# and08479_Individual.net
KiCad netlist of a schematic drawn in Altium Designer
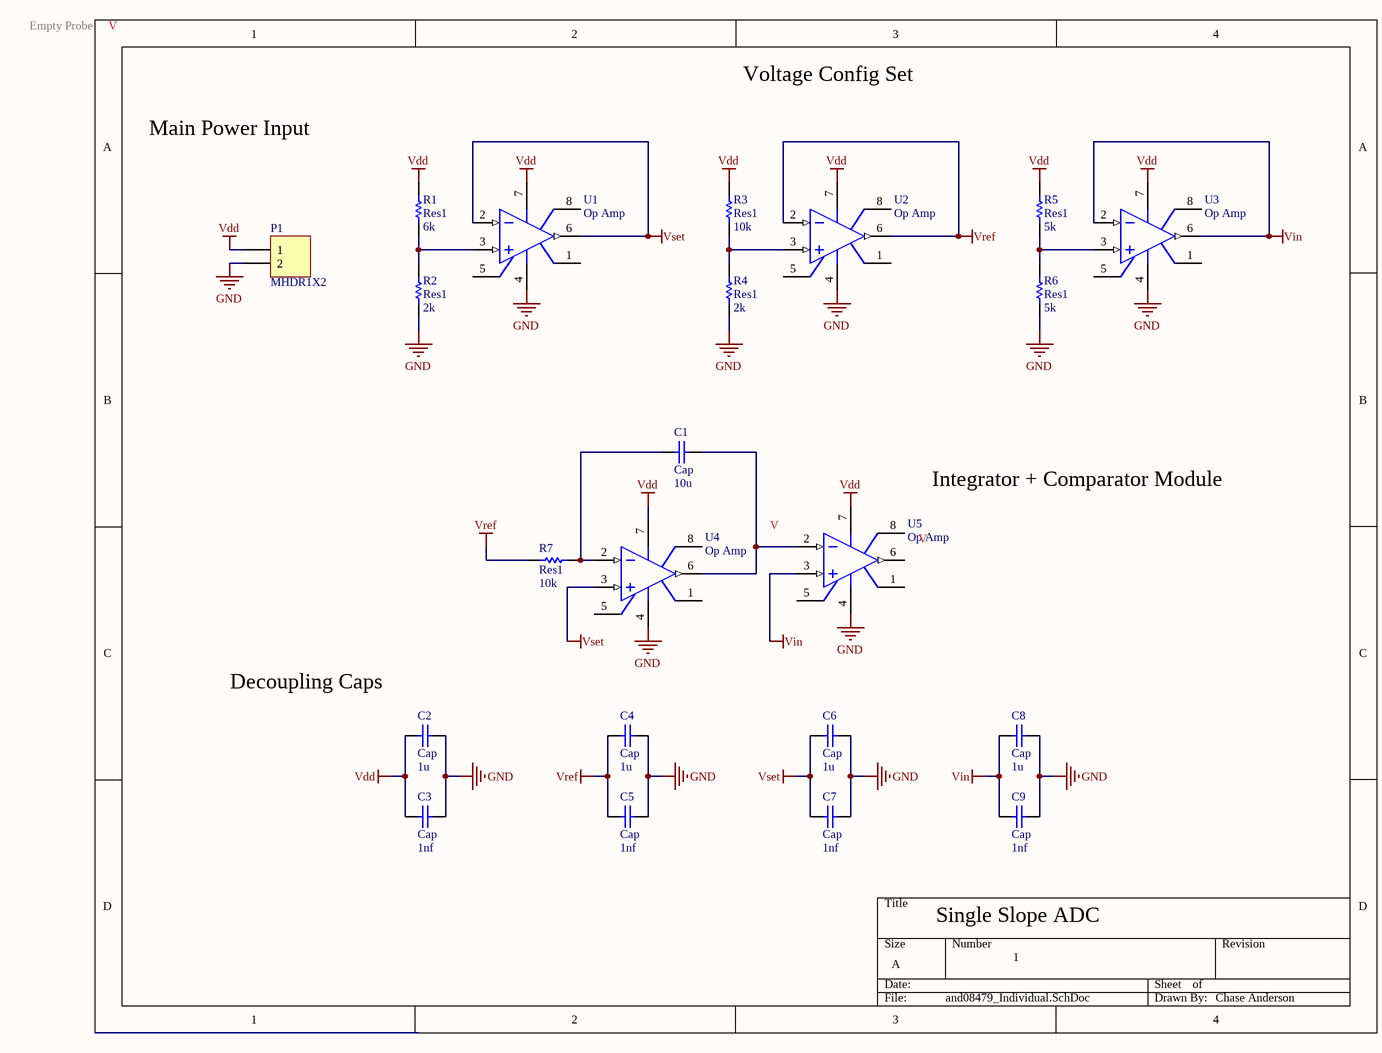
[diagram p0: and08479_Individual.SchDoc]

(export (version "E")
  (design (tool "Eeschema 10.0.6"))
  (components
    (comp (ref "C1")
      (value "Cap")
      (footprint "RAD-0.3")
      (description "Capacitor")
      (fields (field (name "ALTIUM_VALUE") "10u") (field (name "PUBLISHER") "Altium Limited"))
      (libsource (lib "Miscellaneous Devices") (part "Cap"))
    )
    (comp (ref "C2")
      (value "Cap")
      (footprint "RAD-0.3")
      (description "Capacitor")
      (fields (field (name "ALTIUM_VALUE") "1u") (field (name "PUBLISHER") "Altium Limited"))
      (libsource (lib "Miscellaneous Devices") (part "Cap"))
    )
    (comp (ref "C3")
      (value "Cap")
      (footprint "RAD-0.3")
      (description "Capacitor")
      (fields (field (name "ALTIUM_VALUE") "1nf") (field (name "PUBLISHER") "Altium Limited"))
      (libsource (lib "Miscellaneous Devices") (part "Cap"))
    )
    (comp (ref "C4")
      (value "Cap")
      (footprint "RAD-0.3")
      (description "Capacitor")
      (fields (field (name "ALTIUM_VALUE") "1u") (field (name "PUBLISHER") "Altium Limited"))
      (libsource (lib "Miscellaneous Devices") (part "Cap"))
    )
    (comp (ref "C5")
      (value "Cap")
      (footprint "RAD-0.3")
      (description "Capacitor")
      (fields (field (name "ALTIUM_VALUE") "1nf") (field (name "PUBLISHER") "Altium Limited"))
      (libsource (lib "Miscellaneous Devices") (part "Cap"))
    )
    (comp (ref "C6")
      (value "Cap")
      (footprint "RAD-0.3")
      (description "Capacitor")
      (fields (field (name "ALTIUM_VALUE") "1u") (field (name "PUBLISHER") "Altium Limited"))
      (libsource (lib "Miscellaneous Devices") (part "Cap"))
    )
    (comp (ref "C7")
      (value "Cap")
      (footprint "RAD-0.3")
      (description "Capacitor")
      (fields (field (name "ALTIUM_VALUE") "1nf") (field (name "PUBLISHER") "Altium Limited"))
      (libsource (lib "Miscellaneous Devices") (part "Cap"))
    )
    (comp (ref "C8")
      (value "Cap")
      (footprint "RAD-0.3")
      (description "Capacitor")
      (fields (field (name "ALTIUM_VALUE") "1u") (field (name "PUBLISHER") "Altium Limited"))
      (libsource (lib "Miscellaneous Devices") (part "Cap"))
    )
    (comp (ref "C9")
      (value "Cap")
      (footprint "RAD-0.3")
      (description "Capacitor")
      (fields (field (name "ALTIUM_VALUE") "1nf") (field (name "PUBLISHER") "Altium Limited"))
      (libsource (lib "Miscellaneous Devices") (part "Cap"))
    )
    (comp (ref "P1")
      (value "MHDR1X2")
      (footprint "MHDR1X2")
      (description "Header, 2-Pin")
      (fields (field (name "PUBLISHER") "Altium Limited"))
      (libsource (lib "Miscellaneous Connectors") (part "MHDR1X2"))
    )
    (comp (ref "R1")
      (value "Res1")
      (footprint "AXIAL-0.3")
      (description "Resistor")
      (fields (field (name "ALTIUM_VALUE") "6k") (field (name "PUBLISHER") "Altium Limited"))
      (libsource (lib "Miscellaneous Devices") (part "Res1"))
    )
    (comp (ref "R2")
      (value "Res1")
      (footprint "AXIAL-0.3")
      (description "Resistor")
      (fields (field (name "ALTIUM_VALUE") "2k") (field (name "PUBLISHER") "Altium Limited"))
      (libsource (lib "Miscellaneous Devices") (part "Res1"))
    )
    (comp (ref "R3")
      (value "Res1")
      (footprint "AXIAL-0.3")
      (description "Resistor")
      (fields (field (name "ALTIUM_VALUE") "10k") (field (name "PUBLISHER") "Altium Limited"))
      (libsource (lib "Miscellaneous Devices") (part "Res1"))
    )
    (comp (ref "R4")
      (value "Res1")
      (footprint "AXIAL-0.3")
      (description "Resistor")
      (fields (field (name "ALTIUM_VALUE") "2k") (field (name "PUBLISHER") "Altium Limited"))
      (libsource (lib "Miscellaneous Devices") (part "Res1"))
    )
    (comp (ref "R5")
      (value "Res1")
      (footprint "AXIAL-0.3")
      (description "Resistor")
      (fields (field (name "ALTIUM_VALUE") "5k") (field (name "PUBLISHER") "Altium Limited"))
      (libsource (lib "Miscellaneous Devices") (part "Res1"))
    )
    (comp (ref "R6")
      (value "Res1")
      (footprint "AXIAL-0.3")
      (description "Resistor")
      (fields (field (name "ALTIUM_VALUE") "5k") (field (name "PUBLISHER") "Altium Limited"))
      (libsource (lib "Miscellaneous Devices") (part "Res1"))
    )
    (comp (ref "R7")
      (value "Res1")
      (footprint "AXIAL-0.3")
      (description "Resistor")
      (fields (field (name "ALTIUM_VALUE") "10k") (field (name "PUBLISHER") "Altium Limited"))
      (libsource (lib "Miscellaneous Devices") (part "Res1"))
    )
    (comp (ref "U1")
      (value "Op Amp")
      (footprint "H-08A")
      (description "FET Operational Amplifier")
      (fields (field (name "PUBLISHER") "Altium Limited"))
      (libsource (lib "Miscellaneous Devices") (part "Op Amp"))
    )
    (comp (ref "U2")
      (value "Op Amp")
      (footprint "H-08A")
      (description "FET Operational Amplifier")
      (fields (field (name "PUBLISHER") "Altium Limited"))
      (libsource (lib "Miscellaneous Devices") (part "Op Amp"))
    )
    (comp (ref "U3")
      (value "Op Amp")
      (footprint "H-08A")
      (description "FET Operational Amplifier")
      (fields (field (name "PUBLISHER") "Altium Limited"))
      (libsource (lib "Miscellaneous Devices") (part "Op Amp"))
    )
    (comp (ref "U4")
      (value "Op Amp")
      (footprint "H-08A")
      (description "FET Operational Amplifier")
      (fields (field (name "PUBLISHER") "Altium Limited"))
      (libsource (lib "Miscellaneous Devices") (part "Op Amp"))
    )
    (comp (ref "U5")
      (value "Op Amp")
      (footprint "H-08A")
      (description "FET Operational Amplifier")
      (fields (field (name "PUBLISHER") "Altium Limited"))
      (libsource (lib "Miscellaneous Devices") (part "Op Amp"))
    )
  )
  (nets
    (net (code "1") (name "GND") (class "Default")
      (node (ref "C2") (pin "2") (pinfunction "2_2") (pintype "passive"))
      (node (ref "C3") (pin "2") (pinfunction "2_2") (pintype "passive"))
      (node (ref "C4") (pin "2") (pinfunction "2_2") (pintype "passive"))
      (node (ref "C5") (pin "2") (pinfunction "2_2") (pintype "passive"))
      (node (ref "C6") (pin "2") (pinfunction "2_2") (pintype "passive"))
      (node (ref "C7") (pin "2") (pinfunction "2_2") (pintype "passive"))
      (node (ref "C8") (pin "2") (pinfunction "2_2") (pintype "passive"))
      (node (ref "C9") (pin "2") (pinfunction "2_2") (pintype "passive"))
      (node (ref "P1") (pin "2") (pinfunction "2_2") (pintype "passive"))
      (node (ref "R2") (pin "1") (pinfunction "1_1") (pintype "passive"))
      (node (ref "R4") (pin "1") (pinfunction "1_1") (pintype "passive"))
      (node (ref "R6") (pin "1") (pinfunction "1_1") (pintype "passive"))
      (node (ref "U1") (pin "4") (pinfunction "V-_4") (pintype "power_in"))
      (node (ref "U2") (pin "4") (pinfunction "V-_4") (pintype "power_in"))
      (node (ref "U3") (pin "4") (pinfunction "V-_4") (pintype "power_in"))
      (node (ref "U4") (pin "4") (pinfunction "V-_4") (pintype "power_in"))
      (node (ref "U5") (pin "4") (pinfunction "V-_4") (pintype "power_in"))
    )
    (net (code "2") (name "Net-(U1-IN+)") (class "Default")
      (node (ref "R1") (pin "1") (pinfunction "1_1") (pintype "passive"))
      (node (ref "R2") (pin "2") (pinfunction "2_2") (pintype "passive"))
      (node (ref "U1") (pin "3") (pinfunction "IN+_3") (pintype "input"))
    )
    (net (code "3") (name "Net-(U2-IN+)") (class "Default")
      (node (ref "R3") (pin "1") (pinfunction "1_1") (pintype "passive"))
      (node (ref "R4") (pin "2") (pinfunction "2_2") (pintype "passive"))
      (node (ref "U2") (pin "3") (pinfunction "IN+_3") (pintype "input"))
    )
    (net (code "4") (name "Net-(U3-IN+)") (class "Default")
      (node (ref "R5") (pin "1") (pinfunction "1_1") (pintype "passive"))
      (node (ref "R6") (pin "2") (pinfunction "2_2") (pintype "passive"))
      (node (ref "U3") (pin "3") (pinfunction "IN+_3") (pintype "input"))
    )
    (net (code "5") (name "Net-(U4-IN-)") (class "Default")
      (node (ref "C1") (pin "1") (pinfunction "1_1") (pintype "passive"))
      (node (ref "R7") (pin "2") (pinfunction "2_2") (pintype "passive"))
      (node (ref "U4") (pin "2") (pinfunction "IN-_2") (pintype "input"))
    )
    (net (code "6") (name "Net-(U4-OUT)") (class "Default")
      (node (ref "C1") (pin "2") (pinfunction "2_2") (pintype "passive"))
      (node (ref "U4") (pin "6") (pinfunction "OUT_6") (pintype "output"))
      (node (ref "U5") (pin "2") (pinfunction "IN-_2") (pintype "input"))
    )
    (net (code "7") (name "Vdd") (class "Default")
      (node (ref "C2") (pin "1") (pinfunction "1_1") (pintype "passive"))
      (node (ref "C3") (pin "1") (pinfunction "1_1") (pintype "passive"))
      (node (ref "P1") (pin "1") (pinfunction "1_1") (pintype "passive"))
      (node (ref "R1") (pin "2") (pinfunction "2_2") (pintype "passive"))
      (node (ref "R3") (pin "2") (pinfunction "2_2") (pintype "passive"))
      (node (ref "R5") (pin "2") (pinfunction "2_2") (pintype "passive"))
      (node (ref "U1") (pin "7") (pinfunction "V+_7") (pintype "power_in"))
      (node (ref "U2") (pin "7") (pinfunction "V+_7") (pintype "power_in"))
      (node (ref "U3") (pin "7") (pinfunction "V+_7") (pintype "power_in"))
      (node (ref "U4") (pin "7") (pinfunction "V+_7") (pintype "power_in"))
      (node (ref "U5") (pin "7") (pinfunction "V+_7") (pintype "power_in"))
    )
    (net (code "8") (name "Vin") (class "Default")
      (node (ref "C8") (pin "1") (pinfunction "1_1") (pintype "passive"))
      (node (ref "C9") (pin "1") (pinfunction "1_1") (pintype "passive"))
      (node (ref "U3") (pin "2") (pinfunction "IN-_2") (pintype "input"))
      (node (ref "U3") (pin "6") (pinfunction "OUT_6") (pintype "output"))
      (node (ref "U5") (pin "3") (pinfunction "IN+_3") (pintype "input"))
    )
    (net (code "9") (name "Vref") (class "Default")
      (node (ref "C4") (pin "1") (pinfunction "1_1") (pintype "passive"))
      (node (ref "C5") (pin "1") (pinfunction "1_1") (pintype "passive"))
      (node (ref "R7") (pin "1") (pinfunction "1_1") (pintype "passive"))
      (node (ref "U2") (pin "2") (pinfunction "IN-_2") (pintype "input"))
      (node (ref "U2") (pin "6") (pinfunction "OUT_6") (pintype "output"))
    )
    (net (code "10") (name "Vset") (class "Default")
      (node (ref "C6") (pin "1") (pinfunction "1_1") (pintype "passive"))
      (node (ref "C7") (pin "1") (pinfunction "1_1") (pintype "passive"))
      (node (ref "U1") (pin "2") (pinfunction "IN-_2") (pintype "input"))
      (node (ref "U1") (pin "6") (pinfunction "OUT_6") (pintype "output"))
      (node (ref "U4") (pin "3") (pinfunction "IN+_3") (pintype "input"))
    )
    (net (code "11") (name "unconnected-(U1-OS_NUL-Pad1)") (class "Default")
      (node (ref "U1") (pin "1") (pinfunction "OS_NUL_1") (pintype "passive"))
    )
    (net (code "12") (name "unconnected-(U1-OS_NUL-Pad5)") (class "Default")
      (node (ref "U1") (pin "5") (pinfunction "OS_NUL_5") (pintype "passive"))
    )
    (net (code "13") (name "unconnected-(U1-TAB-Pad8)") (class "Default")
      (node (ref "U1") (pin "8") (pinfunction "TAB_8") (pintype "passive"))
    )
    (net (code "14") (name "unconnected-(U2-OS_NUL-Pad1)") (class "Default")
      (node (ref "U2") (pin "1") (pinfunction "OS_NUL_1") (pintype "passive"))
    )
    (net (code "15") (name "unconnected-(U2-OS_NUL-Pad5)") (class "Default")
      (node (ref "U2") (pin "5") (pinfunction "OS_NUL_5") (pintype "passive"))
    )
    (net (code "16") (name "unconnected-(U2-TAB-Pad8)") (class "Default")
      (node (ref "U2") (pin "8") (pinfunction "TAB_8") (pintype "passive"))
    )
    (net (code "17") (name "unconnected-(U3-OS_NUL-Pad1)") (class "Default")
      (node (ref "U3") (pin "1") (pinfunction "OS_NUL_1") (pintype "passive"))
    )
    (net (code "18") (name "unconnected-(U3-OS_NUL-Pad5)") (class "Default")
      (node (ref "U3") (pin "5") (pinfunction "OS_NUL_5") (pintype "passive"))
    )
    (net (code "19") (name "unconnected-(U3-TAB-Pad8)") (class "Default")
      (node (ref "U3") (pin "8") (pinfunction "TAB_8") (pintype "passive"))
    )
    (net (code "20") (name "unconnected-(U4-OS_NUL-Pad1)") (class "Default")
      (node (ref "U4") (pin "1") (pinfunction "OS_NUL_1") (pintype "passive"))
    )
    (net (code "21") (name "unconnected-(U4-OS_NUL-Pad5)") (class "Default")
      (node (ref "U4") (pin "5") (pinfunction "OS_NUL_5") (pintype "passive"))
    )
    (net (code "22") (name "unconnected-(U4-TAB-Pad8)") (class "Default")
      (node (ref "U4") (pin "8") (pinfunction "TAB_8") (pintype "passive"))
    )
    (net (code "23") (name "unconnected-(U5-OS_NUL-Pad1)") (class "Default")
      (node (ref "U5") (pin "1") (pinfunction "OS_NUL_1") (pintype "passive"))
    )
    (net (code "24") (name "unconnected-(U5-OS_NUL-Pad5)") (class "Default")
      (node (ref "U5") (pin "5") (pinfunction "OS_NUL_5") (pintype "passive"))
    )
    (net (code "25") (name "unconnected-(U5-OUT-Pad6)") (class "Default")
      (node (ref "U5") (pin "6") (pinfunction "OUT_6") (pintype "output"))
    )
    (net (code "26") (name "unconnected-(U5-TAB-Pad8)") (class "Default")
      (node (ref "U5") (pin "8") (pinfunction "TAB_8") (pintype "passive"))
    )
  )
)
